# AxionAdapterPogo.net
KiCad netlist of a schematic drawn in EAGLE
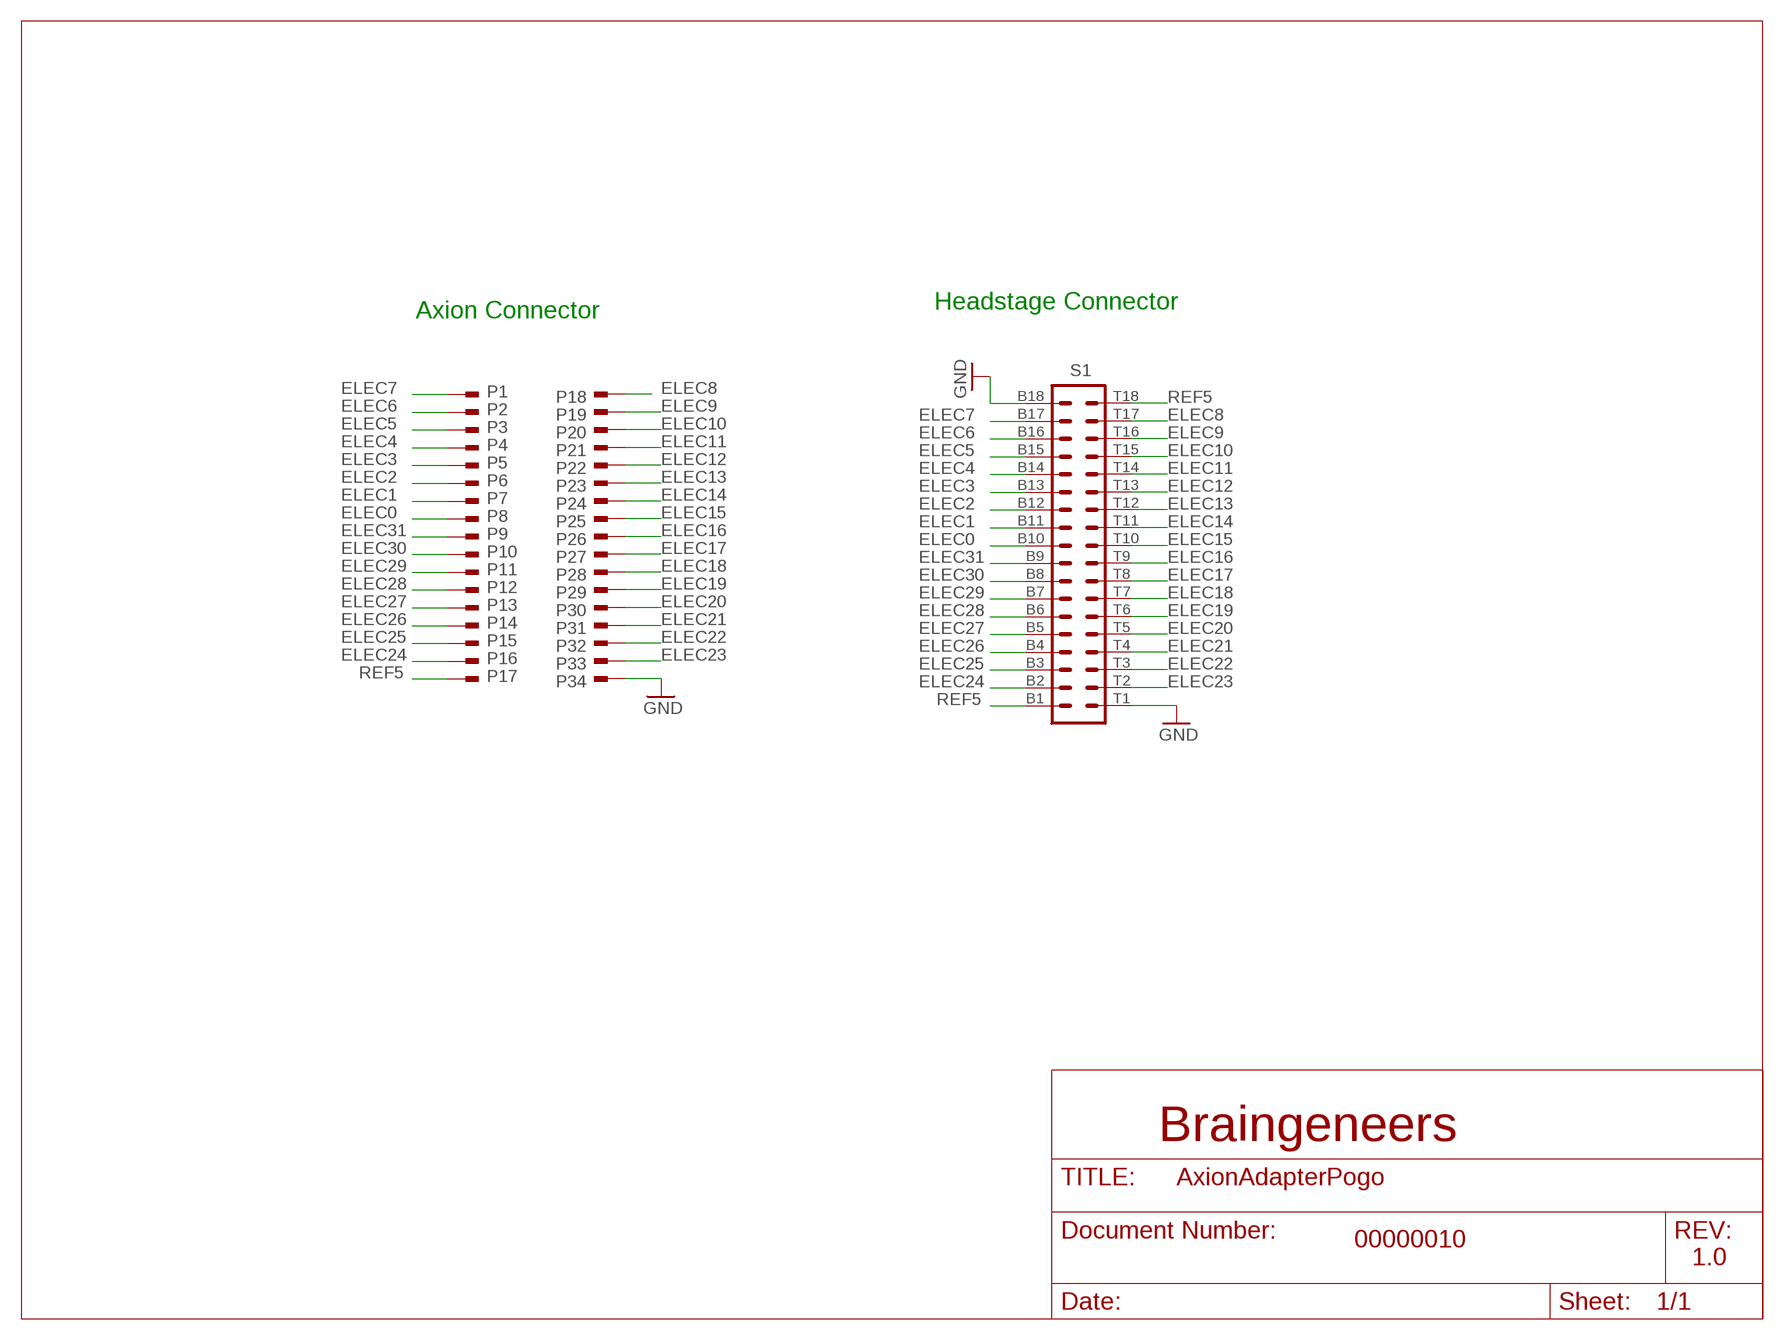
[diagram p0: schematic, sheet 1]

(export (version "E")
  (design (tool "Eeschema 10.0.6"))
  (components
    (comp (ref "P1")
      (value "MILL-MAX_POGO_0985-0-15-20-71-14-11-0")
      (footprint "eagle-import:MILL-MAX_POGO_0985-0-15-20-71-14-11-0")
      (libsource (lib "eagle-import") (part "MILL-MAX_POGO_0985-0-15-20-71-14-11-0"))
    )
    (comp (ref "P2")
      (value "MILL-MAX_POGO_0985-0-15-20-71-14-11-0")
      (footprint "eagle-import:MILL-MAX_POGO_0985-0-15-20-71-14-11-0")
      (libsource (lib "eagle-import") (part "MILL-MAX_POGO_0985-0-15-20-71-14-11-0"))
    )
    (comp (ref "P3")
      (value "MILL-MAX_POGO_0985-0-15-20-71-14-11-0")
      (footprint "eagle-import:MILL-MAX_POGO_0985-0-15-20-71-14-11-0")
      (libsource (lib "eagle-import") (part "MILL-MAX_POGO_0985-0-15-20-71-14-11-0"))
    )
    (comp (ref "P4")
      (value "MILL-MAX_POGO_0985-0-15-20-71-14-11-0")
      (footprint "eagle-import:MILL-MAX_POGO_0985-0-15-20-71-14-11-0")
      (libsource (lib "eagle-import") (part "MILL-MAX_POGO_0985-0-15-20-71-14-11-0"))
    )
    (comp (ref "P5")
      (value "MILL-MAX_POGO_0985-0-15-20-71-14-11-0")
      (footprint "eagle-import:MILL-MAX_POGO_0985-0-15-20-71-14-11-0")
      (libsource (lib "eagle-import") (part "MILL-MAX_POGO_0985-0-15-20-71-14-11-0"))
    )
    (comp (ref "P6")
      (value "MILL-MAX_POGO_0985-0-15-20-71-14-11-0")
      (footprint "eagle-import:MILL-MAX_POGO_0985-0-15-20-71-14-11-0")
      (libsource (lib "eagle-import") (part "MILL-MAX_POGO_0985-0-15-20-71-14-11-0"))
    )
    (comp (ref "P7")
      (value "MILL-MAX_POGO_0985-0-15-20-71-14-11-0")
      (footprint "eagle-import:MILL-MAX_POGO_0985-0-15-20-71-14-11-0")
      (libsource (lib "eagle-import") (part "MILL-MAX_POGO_0985-0-15-20-71-14-11-0"))
    )
    (comp (ref "P8")
      (value "MILL-MAX_POGO_0985-0-15-20-71-14-11-0")
      (footprint "eagle-import:MILL-MAX_POGO_0985-0-15-20-71-14-11-0")
      (libsource (lib "eagle-import") (part "MILL-MAX_POGO_0985-0-15-20-71-14-11-0"))
    )
    (comp (ref "P9")
      (value "MILL-MAX_POGO_0985-0-15-20-71-14-11-0")
      (footprint "eagle-import:MILL-MAX_POGO_0985-0-15-20-71-14-11-0")
      (libsource (lib "eagle-import") (part "MILL-MAX_POGO_0985-0-15-20-71-14-11-0"))
    )
    (comp (ref "P10")
      (value "MILL-MAX_POGO_0985-0-15-20-71-14-11-0")
      (footprint "eagle-import:MILL-MAX_POGO_0985-0-15-20-71-14-11-0")
      (libsource (lib "eagle-import") (part "MILL-MAX_POGO_0985-0-15-20-71-14-11-0"))
    )
    (comp (ref "P11")
      (value "MILL-MAX_POGO_0985-0-15-20-71-14-11-0")
      (footprint "eagle-import:MILL-MAX_POGO_0985-0-15-20-71-14-11-0")
      (libsource (lib "eagle-import") (part "MILL-MAX_POGO_0985-0-15-20-71-14-11-0"))
    )
    (comp (ref "P12")
      (value "MILL-MAX_POGO_0985-0-15-20-71-14-11-0")
      (footprint "eagle-import:MILL-MAX_POGO_0985-0-15-20-71-14-11-0")
      (libsource (lib "eagle-import") (part "MILL-MAX_POGO_0985-0-15-20-71-14-11-0"))
    )
    (comp (ref "P13")
      (value "MILL-MAX_POGO_0985-0-15-20-71-14-11-0")
      (footprint "eagle-import:MILL-MAX_POGO_0985-0-15-20-71-14-11-0")
      (libsource (lib "eagle-import") (part "MILL-MAX_POGO_0985-0-15-20-71-14-11-0"))
    )
    (comp (ref "P14")
      (value "MILL-MAX_POGO_0985-0-15-20-71-14-11-0")
      (footprint "eagle-import:MILL-MAX_POGO_0985-0-15-20-71-14-11-0")
      (libsource (lib "eagle-import") (part "MILL-MAX_POGO_0985-0-15-20-71-14-11-0"))
    )
    (comp (ref "P15")
      (value "MILL-MAX_POGO_0985-0-15-20-71-14-11-0")
      (footprint "eagle-import:MILL-MAX_POGO_0985-0-15-20-71-14-11-0")
      (libsource (lib "eagle-import") (part "MILL-MAX_POGO_0985-0-15-20-71-14-11-0"))
    )
    (comp (ref "P16")
      (value "MILL-MAX_POGO_0985-0-15-20-71-14-11-0")
      (footprint "eagle-import:MILL-MAX_POGO_0985-0-15-20-71-14-11-0")
      (libsource (lib "eagle-import") (part "MILL-MAX_POGO_0985-0-15-20-71-14-11-0"))
    )
    (comp (ref "P17")
      (value "MILL-MAX_POGO_0985-0-15-20-71-14-11-0")
      (footprint "eagle-import:MILL-MAX_POGO_0985-0-15-20-71-14-11-0")
      (libsource (lib "eagle-import") (part "MILL-MAX_POGO_0985-0-15-20-71-14-11-0"))
    )
    (comp (ref "P18")
      (value "MILL-MAX_POGO_0985-0-15-20-71-14-11-0")
      (footprint "eagle-import:MILL-MAX_POGO_0985-0-15-20-71-14-11-0")
      (libsource (lib "eagle-import") (part "MILL-MAX_POGO_0985-0-15-20-71-14-11-0"))
    )
    (comp (ref "P19")
      (value "MILL-MAX_POGO_0985-0-15-20-71-14-11-0")
      (footprint "eagle-import:MILL-MAX_POGO_0985-0-15-20-71-14-11-0")
      (libsource (lib "eagle-import") (part "MILL-MAX_POGO_0985-0-15-20-71-14-11-0"))
    )
    (comp (ref "P20")
      (value "MILL-MAX_POGO_0985-0-15-20-71-14-11-0")
      (footprint "eagle-import:MILL-MAX_POGO_0985-0-15-20-71-14-11-0")
      (libsource (lib "eagle-import") (part "MILL-MAX_POGO_0985-0-15-20-71-14-11-0"))
    )
    (comp (ref "P21")
      (value "MILL-MAX_POGO_0985-0-15-20-71-14-11-0")
      (footprint "eagle-import:MILL-MAX_POGO_0985-0-15-20-71-14-11-0")
      (libsource (lib "eagle-import") (part "MILL-MAX_POGO_0985-0-15-20-71-14-11-0"))
    )
    (comp (ref "P22")
      (value "MILL-MAX_POGO_0985-0-15-20-71-14-11-0")
      (footprint "eagle-import:MILL-MAX_POGO_0985-0-15-20-71-14-11-0")
      (libsource (lib "eagle-import") (part "MILL-MAX_POGO_0985-0-15-20-71-14-11-0"))
    )
    (comp (ref "P23")
      (value "MILL-MAX_POGO_0985-0-15-20-71-14-11-0")
      (footprint "eagle-import:MILL-MAX_POGO_0985-0-15-20-71-14-11-0")
      (libsource (lib "eagle-import") (part "MILL-MAX_POGO_0985-0-15-20-71-14-11-0"))
    )
    (comp (ref "P24")
      (value "MILL-MAX_POGO_0985-0-15-20-71-14-11-0")
      (footprint "eagle-import:MILL-MAX_POGO_0985-0-15-20-71-14-11-0")
      (libsource (lib "eagle-import") (part "MILL-MAX_POGO_0985-0-15-20-71-14-11-0"))
    )
    (comp (ref "P25")
      (value "MILL-MAX_POGO_0985-0-15-20-71-14-11-0")
      (footprint "eagle-import:MILL-MAX_POGO_0985-0-15-20-71-14-11-0")
      (libsource (lib "eagle-import") (part "MILL-MAX_POGO_0985-0-15-20-71-14-11-0"))
    )
    (comp (ref "P26")
      (value "MILL-MAX_POGO_0985-0-15-20-71-14-11-0")
      (footprint "eagle-import:MILL-MAX_POGO_0985-0-15-20-71-14-11-0")
      (libsource (lib "eagle-import") (part "MILL-MAX_POGO_0985-0-15-20-71-14-11-0"))
    )
    (comp (ref "P27")
      (value "MILL-MAX_POGO_0985-0-15-20-71-14-11-0")
      (footprint "eagle-import:MILL-MAX_POGO_0985-0-15-20-71-14-11-0")
      (libsource (lib "eagle-import") (part "MILL-MAX_POGO_0985-0-15-20-71-14-11-0"))
    )
    (comp (ref "P28")
      (value "MILL-MAX_POGO_0985-0-15-20-71-14-11-0")
      (footprint "eagle-import:MILL-MAX_POGO_0985-0-15-20-71-14-11-0")
      (libsource (lib "eagle-import") (part "MILL-MAX_POGO_0985-0-15-20-71-14-11-0"))
    )
    (comp (ref "P29")
      (value "MILL-MAX_POGO_0985-0-15-20-71-14-11-0")
      (footprint "eagle-import:MILL-MAX_POGO_0985-0-15-20-71-14-11-0")
      (libsource (lib "eagle-import") (part "MILL-MAX_POGO_0985-0-15-20-71-14-11-0"))
    )
    (comp (ref "P30")
      (value "MILL-MAX_POGO_0985-0-15-20-71-14-11-0")
      (footprint "eagle-import:MILL-MAX_POGO_0985-0-15-20-71-14-11-0")
      (libsource (lib "eagle-import") (part "MILL-MAX_POGO_0985-0-15-20-71-14-11-0"))
    )
    (comp (ref "P31")
      (value "MILL-MAX_POGO_0985-0-15-20-71-14-11-0")
      (footprint "eagle-import:MILL-MAX_POGO_0985-0-15-20-71-14-11-0")
      (libsource (lib "eagle-import") (part "MILL-MAX_POGO_0985-0-15-20-71-14-11-0"))
    )
    (comp (ref "P32")
      (value "MILL-MAX_POGO_0985-0-15-20-71-14-11-0")
      (footprint "eagle-import:MILL-MAX_POGO_0985-0-15-20-71-14-11-0")
      (libsource (lib "eagle-import") (part "MILL-MAX_POGO_0985-0-15-20-71-14-11-0"))
    )
    (comp (ref "P33")
      (value "MILL-MAX_POGO_0985-0-15-20-71-14-11-0")
      (footprint "eagle-import:MILL-MAX_POGO_0985-0-15-20-71-14-11-0")
      (libsource (lib "eagle-import") (part "MILL-MAX_POGO_0985-0-15-20-71-14-11-0"))
    )
    (comp (ref "P34")
      (value "MILL-MAX_POGO_0985-0-15-20-71-14-11-0")
      (footprint "eagle-import:MILL-MAX_POGO_0985-0-15-20-71-14-11-0")
      (libsource (lib "eagle-import") (part "MILL-MAX_POGO_0985-0-15-20-71-14-11-0"))
    )
    (comp (ref "S1")
      (value "OMNETICS_A79024")
      (footprint "eagle-import:OMNETICS_A79024")
      (libsource (lib "eagle-import") (part "OMNETICS_A79024"))
    )
  )
  (nets
    (net (code "1") (name "/ELEC0") (class "Default")
      (node (ref "P8") (pin "P$1") (pinfunction "1_P$1") (pintype "passive"))
      (node (ref "S1") (pin "B10") (pinfunction "B10_B10") (pintype "passive"))
    )
    (net (code "2") (name "/ELEC1") (class "Default")
      (node (ref "P7") (pin "P$1") (pinfunction "1_P$1") (pintype "passive"))
      (node (ref "S1") (pin "B11") (pinfunction "B11_B11") (pintype "passive"))
    )
    (net (code "3") (name "/ELEC2") (class "Default")
      (node (ref "P6") (pin "P$1") (pinfunction "1_P$1") (pintype "passive"))
      (node (ref "S1") (pin "B12") (pinfunction "B12_B12") (pintype "passive"))
    )
    (net (code "4") (name "/ELEC3") (class "Default")
      (node (ref "P5") (pin "P$1") (pinfunction "1_P$1") (pintype "passive"))
      (node (ref "S1") (pin "B13") (pinfunction "B13_B13") (pintype "passive"))
    )
    (net (code "5") (name "/ELEC4") (class "Default")
      (node (ref "P4") (pin "P$1") (pinfunction "1_P$1") (pintype "passive"))
      (node (ref "S1") (pin "B14") (pinfunction "B14_B14") (pintype "passive"))
    )
    (net (code "6") (name "/ELEC5") (class "Default")
      (node (ref "P3") (pin "P$1") (pinfunction "1_P$1") (pintype "passive"))
      (node (ref "S1") (pin "B15") (pinfunction "B15_B15") (pintype "passive"))
    )
    (net (code "7") (name "/ELEC6") (class "Default")
      (node (ref "P2") (pin "P$1") (pinfunction "1_P$1") (pintype "passive"))
      (node (ref "S1") (pin "B16") (pinfunction "B16_B16") (pintype "passive"))
    )
    (net (code "8") (name "/ELEC7") (class "Default")
      (node (ref "P1") (pin "P$1") (pinfunction "1_P$1") (pintype "passive"))
      (node (ref "S1") (pin "B17") (pinfunction "B17_B17") (pintype "passive"))
    )
    (net (code "9") (name "/ELEC8") (class "Default")
      (node (ref "P18") (pin "P$1") (pinfunction "1_P$1") (pintype "passive"))
      (node (ref "S1") (pin "T17") (pinfunction "T17_T17") (pintype "passive"))
    )
    (net (code "10") (name "/ELEC9") (class "Default")
      (node (ref "P19") (pin "P$1") (pinfunction "1_P$1") (pintype "passive"))
      (node (ref "S1") (pin "T16") (pinfunction "T16_T16") (pintype "passive"))
    )
    (net (code "11") (name "/ELEC10") (class "Default")
      (node (ref "P20") (pin "P$1") (pinfunction "1_P$1") (pintype "passive"))
      (node (ref "S1") (pin "T15") (pinfunction "T15_T15") (pintype "passive"))
    )
    (net (code "12") (name "/ELEC11") (class "Default")
      (node (ref "P21") (pin "P$1") (pinfunction "1_P$1") (pintype "passive"))
      (node (ref "S1") (pin "T14") (pinfunction "T14_T14") (pintype "passive"))
    )
    (net (code "13") (name "/ELEC12") (class "Default")
      (node (ref "P22") (pin "P$1") (pinfunction "1_P$1") (pintype "passive"))
      (node (ref "S1") (pin "T13") (pinfunction "T13_T13") (pintype "passive"))
    )
    (net (code "14") (name "/ELEC13") (class "Default")
      (node (ref "P23") (pin "P$1") (pinfunction "1_P$1") (pintype "passive"))
      (node (ref "S1") (pin "T12") (pinfunction "T12_T12") (pintype "passive"))
    )
    (net (code "15") (name "/ELEC14") (class "Default")
      (node (ref "P24") (pin "P$1") (pinfunction "1_P$1") (pintype "passive"))
      (node (ref "S1") (pin "T11") (pinfunction "T11_T11") (pintype "passive"))
    )
    (net (code "16") (name "/ELEC15") (class "Default")
      (node (ref "P25") (pin "P$1") (pinfunction "1_P$1") (pintype "passive"))
      (node (ref "S1") (pin "T10") (pinfunction "T10_T10") (pintype "passive"))
    )
    (net (code "17") (name "/ELEC16") (class "Default")
      (node (ref "P26") (pin "P$1") (pinfunction "1_P$1") (pintype "passive"))
      (node (ref "S1") (pin "T9") (pinfunction "T9_T9") (pintype "passive"))
    )
    (net (code "18") (name "/ELEC17") (class "Default")
      (node (ref "P27") (pin "P$1") (pinfunction "1_P$1") (pintype "passive"))
      (node (ref "S1") (pin "T8") (pinfunction "T8_T8") (pintype "passive"))
    )
    (net (code "19") (name "/ELEC18") (class "Default")
      (node (ref "P28") (pin "P$1") (pinfunction "1_P$1") (pintype "passive"))
      (node (ref "S1") (pin "T7") (pinfunction "T7_T7") (pintype "passive"))
    )
    (net (code "20") (name "/ELEC19") (class "Default")
      (node (ref "P29") (pin "P$1") (pinfunction "1_P$1") (pintype "passive"))
      (node (ref "S1") (pin "T6") (pinfunction "T6_T6") (pintype "passive"))
    )
    (net (code "21") (name "/ELEC20") (class "Default")
      (node (ref "P30") (pin "P$1") (pinfunction "1_P$1") (pintype "passive"))
      (node (ref "S1") (pin "T5") (pinfunction "T5_T5") (pintype "passive"))
    )
    (net (code "22") (name "/ELEC21") (class "Default")
      (node (ref "P31") (pin "P$1") (pinfunction "1_P$1") (pintype "passive"))
      (node (ref "S1") (pin "T4") (pinfunction "T4_T4") (pintype "passive"))
    )
    (net (code "23") (name "/ELEC22") (class "Default")
      (node (ref "P32") (pin "P$1") (pinfunction "1_P$1") (pintype "passive"))
      (node (ref "S1") (pin "T3") (pinfunction "T3_T3") (pintype "passive"))
    )
    (net (code "24") (name "/ELEC23") (class "Default")
      (node (ref "P33") (pin "P$1") (pinfunction "1_P$1") (pintype "passive"))
      (node (ref "S1") (pin "T2") (pinfunction "T2_T2") (pintype "passive"))
    )
    (net (code "25") (name "/ELEC24") (class "Default")
      (node (ref "P16") (pin "P$1") (pinfunction "1_P$1") (pintype "passive"))
      (node (ref "S1") (pin "B2") (pinfunction "B2_B2") (pintype "passive"))
    )
    (net (code "26") (name "/ELEC25") (class "Default")
      (node (ref "P15") (pin "P$1") (pinfunction "1_P$1") (pintype "passive"))
      (node (ref "S1") (pin "B3") (pinfunction "B3_B3") (pintype "passive"))
    )
    (net (code "27") (name "/ELEC26") (class "Default")
      (node (ref "P14") (pin "P$1") (pinfunction "1_P$1") (pintype "passive"))
      (node (ref "S1") (pin "B4") (pinfunction "B4_B4") (pintype "passive"))
    )
    (net (code "28") (name "/ELEC27") (class "Default")
      (node (ref "P13") (pin "P$1") (pinfunction "1_P$1") (pintype "passive"))
      (node (ref "S1") (pin "B5") (pinfunction "B5_B5") (pintype "passive"))
    )
    (net (code "29") (name "/ELEC28") (class "Default")
      (node (ref "P12") (pin "P$1") (pinfunction "1_P$1") (pintype "passive"))
      (node (ref "S1") (pin "B6") (pinfunction "B6_B6") (pintype "passive"))
    )
    (net (code "30") (name "/ELEC29") (class "Default")
      (node (ref "P11") (pin "P$1") (pinfunction "1_P$1") (pintype "passive"))
      (node (ref "S1") (pin "B7") (pinfunction "B7_B7") (pintype "passive"))
    )
    (net (code "31") (name "/ELEC30") (class "Default")
      (node (ref "P10") (pin "P$1") (pinfunction "1_P$1") (pintype "passive"))
      (node (ref "S1") (pin "B8") (pinfunction "B8_B8") (pintype "passive"))
    )
    (net (code "32") (name "/ELEC31") (class "Default")
      (node (ref "P9") (pin "P$1") (pinfunction "1_P$1") (pintype "passive"))
      (node (ref "S1") (pin "B9") (pinfunction "B9_B9") (pintype "passive"))
    )
    (net (code "33") (name "/REF5") (class "Default")
      (node (ref "P17") (pin "P$1") (pinfunction "1_P$1") (pintype "passive"))
      (node (ref "S1") (pin "B1") (pinfunction "B1_B1") (pintype "passive"))
      (node (ref "S1") (pin "T18") (pinfunction "T18_T18") (pintype "passive"))
    )
    (net (code "34") (name "GND") (class "Default")
      (node (ref "P34") (pin "P$1") (pinfunction "1_P$1") (pintype "passive"))
      (node (ref "S1") (pin "B18") (pinfunction "B18_B18") (pintype "passive"))
      (node (ref "S1") (pin "T1") (pinfunction "T1_T1") (pintype "passive"))
    )
  )
)
